# LED_Driver.net
KiCad netlist of a schematic drawn in Altium Designer
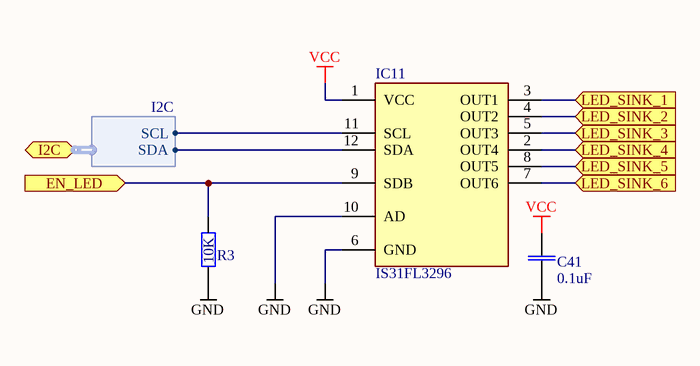
[diagram p0: LED_Driver.SchDoc]

(export (version "E")
  (design (tool "Eeschema 10.0.6"))
  (components
    (comp (ref "C41")
      (value "0.1uF")
      (footprint "CAP0402")
      (fields (field (name "MANUFACTURER") "Samsung Electro-Mechanics"))
      (libsource (lib "Schematic") (part "CAP_0402"))
    )
    (comp (ref "IC11")
      (value "IS31FL3296")
      (footprint "QFN12-2X2(IS31FL3296)")
      (fields (field (name "MANUFACTURER") "Lumissil Microsystems"))
      (libsource (lib "Schematic") (part "IS31FL3296"))
    )
    (comp (ref "R3")
      (value "10K")
      (footprint "RES0402")
      (fields (field (name "MANUFACTURER") "YAGEO"))
      (libsource (lib "Schematic") (part "RES_0402"))
    )
  )
  (nets
    (net (code "2") (name "/EN_LED") (class "Default")
      (node (ref "IC11") (pin "9") (pinfunction "SDB_9") (pintype "passive"))
      (node (ref "R3") (pin "2") (pinfunction "2_2") (pintype "passive"))
    )
    (net (code "3") (name "/LED_SINK_1") (class "Default")
      (node (ref "IC11") (pin "3") (pinfunction "OUT1_3") (pintype "passive"))
    )
    (net (code "4") (name "/LED_SINK_2") (class "Default")
      (node (ref "IC11") (pin "4") (pinfunction "OUT2_4") (pintype "passive"))
    )
    (net (code "5") (name "/LED_SINK_3") (class "Default")
      (node (ref "IC11") (pin "5") (pinfunction "OUT3_5") (pintype "passive"))
    )
    (net (code "6") (name "/LED_SINK_4") (class "Default")
      (node (ref "IC11") (pin "2") (pinfunction "OUT4_2") (pintype "passive"))
    )
    (net (code "7") (name "/LED_SINK_5") (class "Default")
      (node (ref "IC11") (pin "8") (pinfunction "OUT5_8") (pintype "passive"))
    )
    (net (code "8") (name "/LED_SINK_6") (class "Default")
      (node (ref "IC11") (pin "7") (pinfunction "OUT6_7") (pintype "passive"))
    )
    (net (code "9") (name "/SCL") (class "Default")
      (node (ref "IC11") (pin "11") (pinfunction "SCL_11") (pintype "passive"))
    )
    (net (code "10") (name "/SDA") (class "Default")
      (node (ref "IC11") (pin "12") (pinfunction "SDA_12") (pintype "passive"))
    )
    (net (code "12") (name "GND") (class "Default")
      (node (ref "C41") (pin "1") (pinfunction "1_1") (pintype "passive"))
      (node (ref "IC11") (pin "10") (pinfunction "AD_10") (pintype "passive"))
      (node (ref "IC11") (pin "6") (pinfunction "GND_6") (pintype "passive"))
      (node (ref "R3") (pin "1") (pinfunction "1_1") (pintype "passive"))
    )
    (net (code "13") (name "VCC") (class "Default")
      (node (ref "C41") (pin "2") (pinfunction "2_2") (pintype "passive"))
      (node (ref "IC11") (pin "1") (pinfunction "VCC_1") (pintype "passive"))
    )
  )
)
